# sensor_v4_no_gnd.net
KiCad netlist of a schematic drawn in EAGLE
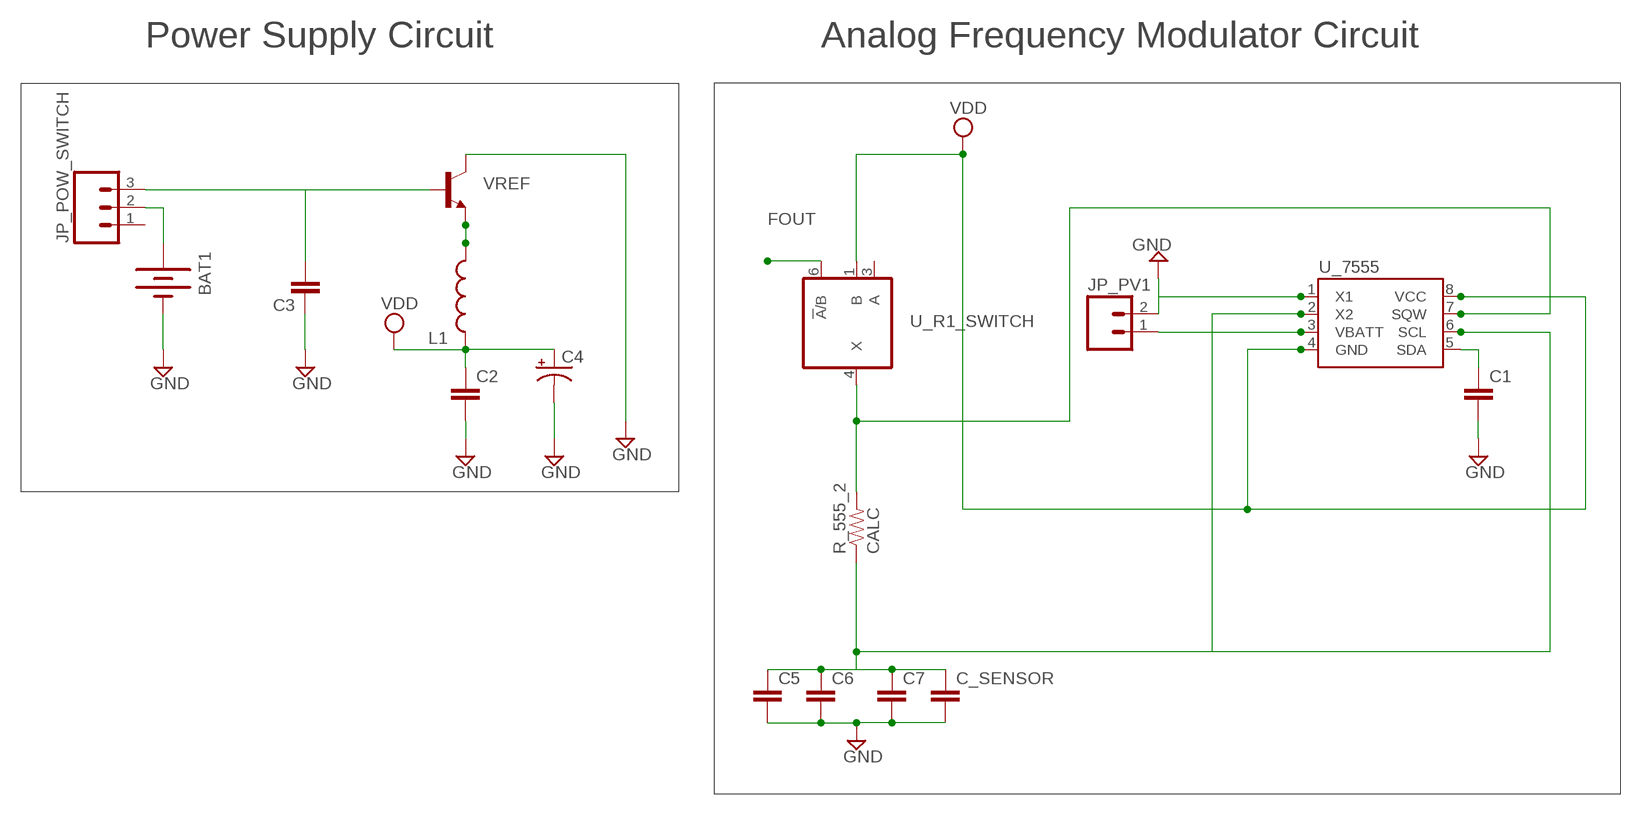
[diagram p0: schematic, sheet 1]

(export (version "E")
  (design (tool "Eeschema 10.0.6"))
  (components
    (comp (ref "BAT1")
      (value "BATTERY20PTH_LAB")
      (footprint "eagle-import:BATTCOM_20MM_PTH")
      (libsource (lib "eagle-import") (part "BATTERY20PTH_LAB"))
    )
    (comp (ref "C1")
      (value "CAP0603-CAP")
      (footprint "eagle-import:0603-CAP")
      (libsource (lib "eagle-import") (part "SparkFun-Capacitors_CAP0603-CAP"))
    )
    (comp (ref "C2")
      (value "CAP0603-CAP")
      (footprint "eagle-import:0603-CAP")
      (libsource (lib "eagle-import") (part "SparkFun-Capacitors_CAP0603-CAP"))
    )
    (comp (ref "C3")
      (value "CAP0603-CAP")
      (footprint "eagle-import:0603-CAP")
      (libsource (lib "eagle-import") (part "SparkFun-Capacitors_CAP0603-CAP"))
    )
    (comp (ref "C4")
      (value "CAP_POL1206")
      (footprint "eagle-import:EIA3216")
      (libsource (lib "eagle-import") (part "CAP_POL1206"))
    )
    (comp (ref "C5")
      (value "CAP0805")
      (footprint "eagle-import:0805")
      (libsource (lib "eagle-import") (part "CAP0805"))
    )
    (comp (ref "C6")
      (value "CAP0805")
      (footprint "eagle-import:0805")
      (libsource (lib "eagle-import") (part "CAP0805"))
    )
    (comp (ref "C7")
      (value "CAP0805")
      (footprint "eagle-import:0805")
      (libsource (lib "eagle-import") (part "CAP0805"))
    )
    (comp (ref "C_SENSOR")
      (value "CAP0805")
      (footprint "eagle-import:0805")
      (libsource (lib "eagle-import") (part "CAP0805"))
    )
    (comp (ref "JP_POW_SWITCH")
      (value "M03LOCK")
      (footprint "eagle-import:1X03_LOCK")
      (libsource (lib "eagle-import") (part "M03LOCK"))
    )
    (comp (ref "JP_PV1")
      (value "M02LOCK")
      (footprint "eagle-import:1X02_LOCK")
      (libsource (lib "eagle-import") (part "M02LOCK"))
    )
    (comp (ref "L1")
      (value "INDUCTOR0603")
      (footprint "eagle-import:0603")
      (libsource (lib "eagle-import") (part "INDUCTOR0603"))
    )
    (comp (ref "R_555_2")
      (value "CALC")
      (footprint "eagle-import:0805")
      (libsource (lib "eagle-import") (part "RESISTOR0805-RES"))
    )
    (comp (ref "U_7555")
      (value "DS1307SO8")
      (footprint "eagle-import:SO08")
      (libsource (lib "eagle-import") (part "DS1307SO8"))
    )
    (comp (ref "U_R1_SWITCH")
      (value "741G3157DCKR")
      (footprint "eagle-import:DCK_R-PDSO-G6")
      (libsource (lib "eagle-import") (part "741G3157DCKR"))
    )
    (comp (ref "U_VREF")
      (value "TRANSISTOR_NPNSOT23-3")
      (footprint "eagle-import:SOT23-3")
      (libsource (lib "eagle-import") (part "TRANSISTOR_NPNSOT23-3"))
    )
  )
  (nets
    (net (code "1") (name "/FOUT") (class "Default")
      (node (ref "JP_PV1") (pin "1") (pinfunction "1_1") (pintype "passive"))
      (node (ref "U_7555") (pin "3") (pinfunction "VBATT_3") (pintype "bidirectional"))
      (node (ref "U_R1_SWITCH") (pin "6") (pinfunction "~{A}/B_6") (pintype "input"))
    )
    (net (code "2") (name "/P2") (class "Default")
      (node (ref "C5") (pin "1") (pinfunction "1_1") (pintype "passive"))
      (node (ref "C6") (pin "1") (pinfunction "1_1") (pintype "passive"))
      (node (ref "C7") (pin "1") (pinfunction "1_1") (pintype "passive"))
      (node (ref "C_SENSOR") (pin "1") (pinfunction "1_1") (pintype "passive"))
      (node (ref "R_555_2") (pin "1") (pinfunction "1_1") (pintype "passive"))
      (node (ref "U_7555") (pin "2") (pinfunction "X2_2") (pintype "bidirectional"))
      (node (ref "U_7555") (pin "6") (pinfunction "SCL_6") (pintype "bidirectional"))
    )
    (net (code "3") (name "GND") (class "Default")
      (node (ref "BAT1") (pin "2") (pinfunction "-_2") (pintype "power_in"))
      (node (ref "C1") (pin "2") (pinfunction "2_2") (pintype "passive"))
      (node (ref "C2") (pin "2") (pinfunction "2_2") (pintype "passive"))
      (node (ref "C3") (pin "1") (pinfunction "1_1") (pintype "passive"))
      (node (ref "C4") (pin "C") (pinfunction "-_C") (pintype "passive"))
      (node (ref "C5") (pin "2") (pinfunction "2_2") (pintype "passive"))
      (node (ref "C6") (pin "2") (pinfunction "2_2") (pintype "passive"))
      (node (ref "C7") (pin "2") (pinfunction "2_2") (pintype "passive"))
      (node (ref "C_SENSOR") (pin "2") (pinfunction "2_2") (pintype "passive"))
      (node (ref "JP_PV1") (pin "2") (pinfunction "2_2") (pintype "passive"))
      (node (ref "U_7555") (pin "1") (pinfunction "X1_1") (pintype "bidirectional"))
      (node (ref "U_VREF") (pin "3") (pinfunction "C_3") (pintype "passive"))
    )
    (net (code "4") (name "Net-(BAT1-+)") (class "Default")
      (node (ref "BAT1") (pin "1") (pinfunction "+_1") (pintype "power_in"))
      (node (ref "JP_POW_SWITCH") (pin "2") (pinfunction "2_2") (pintype "passive"))
    )
    (net (code "5") (name "Net-(U_7555-SDA)") (class "Default")
      (node (ref "C1") (pin "1") (pinfunction "1_1") (pintype "passive"))
      (node (ref "U_7555") (pin "5") (pinfunction "SDA_5") (pintype "bidirectional"))
    )
    (net (code "6") (name "Net-(U_7555-SQW)") (class "Default")
      (node (ref "R_555_2") (pin "2") (pinfunction "2_2") (pintype "passive"))
      (node (ref "U_7555") (pin "7") (pinfunction "SQW_7") (pintype "bidirectional"))
      (node (ref "U_R1_SWITCH") (pin "4") (pinfunction "X_4") (pintype "bidirectional"))
    )
    (net (code "7") (name "Net-(U_VREF-B)") (class "Default")
      (node (ref "C3") (pin "2") (pinfunction "2_2") (pintype "passive"))
      (node (ref "JP_POW_SWITCH") (pin "3") (pinfunction "3_3") (pintype "passive"))
      (node (ref "U_VREF") (pin "1") (pinfunction "B_1") (pintype "passive"))
    )
    (net (code "8") (name "Net-(U_VREF-E)") (class "Default")
      (node (ref "L1") (pin "2") (pinfunction "2_2") (pintype "passive"))
      (node (ref "U_VREF") (pin "2") (pinfunction "E_2") (pintype "passive"))
    )
    (net (code "9") (name "VDD") (class "Default")
      (node (ref "C2") (pin "1") (pinfunction "1_1") (pintype "passive"))
      (node (ref "C4") (pin "A") (pinfunction "+_A") (pintype "passive"))
      (node (ref "L1") (pin "1") (pinfunction "1_1") (pintype "passive"))
      (node (ref "U_7555") (pin "4") (pinfunction "GND_4") (pintype "bidirectional"))
      (node (ref "U_7555") (pin "8") (pinfunction "VCC_8") (pintype "bidirectional"))
      (node (ref "U_R1_SWITCH") (pin "1") (pinfunction "B_1") (pintype "bidirectional"))
    )
    (net (code "10") (name "unconnected-(JP_POW_SWITCH-Pad1)") (class "Default")
      (node (ref "JP_POW_SWITCH") (pin "1") (pinfunction "1_1") (pintype "passive"))
    )
    (net (code "11") (name "unconnected-(U_R1_SWITCHA-A-Pad3)") (class "Default")
      (node (ref "U_R1_SWITCH") (pin "3") (pinfunction "A_3") (pintype "bidirectional"))
    )
  )
)
